# Sheet1.net
KiCad netlist of a schematic drawn in Altium Designer
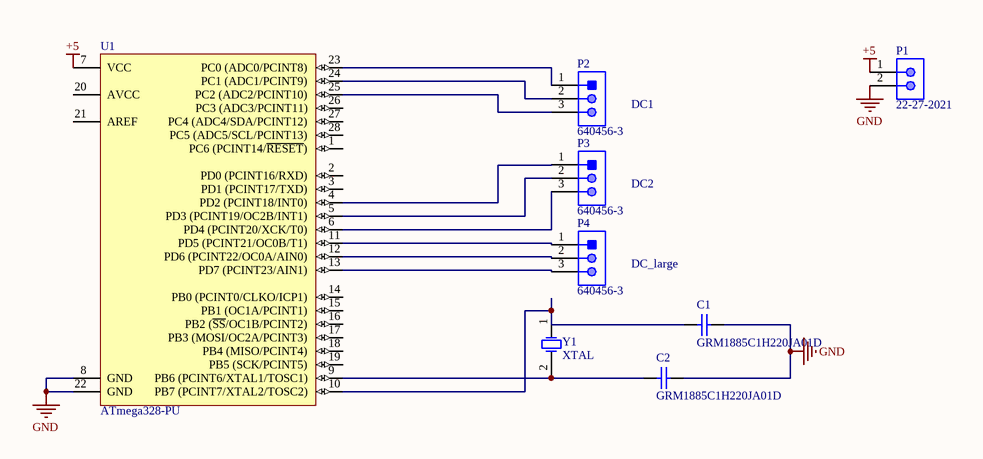
[diagram p0: Sheet1.SchDoc]

(export (version "E")
  (design (tool "Eeschema 10.0.6"))
  (components
    (comp (ref "C1")
      (value "GRM1885C1H220JA01D")
      (footprint "CAPC1608X90X35ML10T15")
      (description "Chip Capacitor, 22 pF, +/- 5%, 50 V, -55 to 125 degC, 0603 (1608 Metric), RoHS, Tape and Reel")
      (fields (field (name "MANUFACTURER") "Murata"))
      (libsource (lib "Altium Content Vault") (part "CAP-NP-2"))
    )
    (comp (ref "C2")
      (value "GRM1885C1H220JA01D")
      (footprint "CAPC1608X90X35ML10T15")
      (description "Chip Capacitor, 22 pF, +/- 5%, 50 V, -55 to 125 degC, 0603 (1608 Metric), RoHS, Tape and Reel")
      (fields (field (name "MANUFACTURER") "Murata"))
      (libsource (lib "Altium Content Vault") (part "CAP-NP-2"))
    )
    (comp (ref "P1")
      (value "22-27-2021")
      (footprint "MOLX-22-27-2021_V")
      (fields (field (name "MANUFACTURER") "Molex") (field (name "PARTNUMBER") "0022272021"))
      (libsource (lib "Altium Content Vault") (part "CN-1P-M-R2"))
    )
    (comp (ref "P2")
      (value "640456-3")
      (footprint "TECO-640456-3")
      (description "Male Header, Pitch 2.54 mm, 1 x 3 Position, Height 10.03 mm, Tail Length 3.56 mm, -55 to 105 degC")
      (fields (field (name "MANUFACTURER") "TE Connectivity"))
      (libsource (lib "Altium Content Vault") (part "CN-1P-M-R3"))
    )
    (comp (ref "P3")
      (value "640456-3")
      (footprint "TECO-640456-3")
      (description "Male Header, Pitch 2.54 mm, 1 x 3 Position, Height 10.03 mm, Tail Length 3.56 mm, -55 to 105 degC")
      (fields (field (name "MANUFACTURER") "TE Connectivity"))
      (libsource (lib "Altium Content Vault") (part "CN-1P-M-R3"))
    )
    (comp (ref "P4")
      (value "640456-3")
      (footprint "TECO-640456-3")
      (description "Male Header, Pitch 2.54 mm, 1 x 3 Position, Height 10.03 mm, Tail Length 3.56 mm, -55 to 105 degC")
      (fields (field (name "MANUFACTURER") "TE Connectivity"))
      (libsource (lib "Altium Content Vault") (part "CN-1P-M-R3"))
    )
    (comp (ref "U1")
      (value "ATmega328-PU")
      (footprint "28P3")
      (libsource (lib "Altium Content Vault") (part "MC-8B-ATM48-IL28"))
    )
    (comp (ref "Y1")
      (value "XTAL")
      (footprint "R38")
      (description "Crystal Oscillator")
      (fields (field (name "PUBLISHER") "Altium Limited"))
      (libsource (lib "Miscellaneous Devices") (part "XTAL"))
    )
  )
  (nets
    (net (code "1") (name "+5") (class "Default")
      (node (ref "P1") (pin "1") (pinfunction "1_1") (pintype "passive"))
      (node (ref "U1") (pin "7") (pinfunction "VCC_7") (pintype "power_in"))
    )
    (net (code "2") (name "GND") (class "Default")
      (node (ref "C1") (pin "2") (pinfunction "2_2") (pintype "passive"))
      (node (ref "C2") (pin "2") (pinfunction "2_2") (pintype "passive"))
      (node (ref "P1") (pin "2") (pinfunction "2_2") (pintype "passive"))
      (node (ref "U1") (pin "22") (pinfunction "GND_22") (pintype "power_in"))
      (node (ref "U1") (pin "8") (pinfunction "GND_8") (pintype "power_in"))
    )
    (net (code "3") (name "Net-(U1-PB6_(PCINT6{slash}XTAL1{slash}TOSC1))") (class "Default")
      (node (ref "C2") (pin "1") (pinfunction "1_1") (pintype "passive"))
      (node (ref "U1") (pin "9") (pinfunction "PB6_(PCINT6/XTAL1/TOSC1)_9") (pintype "bidirectional"))
      (node (ref "Y1") (pin "2") (pinfunction "OSC2_2") (pintype "passive"))
    )
    (net (code "4") (name "Net-(U1-PB7_(PCINT7{slash}XTAL2{slash}TOSC2))") (class "Default")
      (node (ref "C1") (pin "1") (pinfunction "1_1") (pintype "passive"))
      (node (ref "U1") (pin "10") (pinfunction "PB7_(PCINT7/XTAL2/TOSC2)_10") (pintype "bidirectional"))
      (node (ref "Y1") (pin "1") (pinfunction "OSC1_1") (pintype "passive"))
    )
    (net (code "5") (name "Net-(U1-PC0_(ADC0{slash}PCINT8))") (class "Default")
      (node (ref "P2") (pin "1") (pinfunction "1_1") (pintype "passive"))
      (node (ref "U1") (pin "23") (pinfunction "PC0_(ADC0/PCINT8)_23") (pintype "bidirectional"))
    )
    (net (code "6") (name "Net-(U1-PC1_(ADC1{slash}PCINT9))") (class "Default")
      (node (ref "P2") (pin "2") (pinfunction "2_2") (pintype "passive"))
      (node (ref "U1") (pin "24") (pinfunction "PC1_(ADC1/PCINT9)_24") (pintype "bidirectional"))
    )
    (net (code "7") (name "Net-(U1-PC2_(ADC2{slash}PCINT10))") (class "Default")
      (node (ref "P2") (pin "3") (pinfunction "3_3") (pintype "passive"))
      (node (ref "U1") (pin "25") (pinfunction "PC2_(ADC2/PCINT10)_25") (pintype "bidirectional"))
    )
    (net (code "8") (name "Net-(U1-PD2_(PCINT18{slash}INT0))") (class "Default")
      (node (ref "P3") (pin "1") (pinfunction "1_1") (pintype "passive"))
      (node (ref "U1") (pin "4") (pinfunction "PD2_(PCINT18/INT0)_4") (pintype "bidirectional"))
    )
    (net (code "9") (name "Net-(U1-PD3_(PCINT19{slash}OC2B{slash}INT1))") (class "Default")
      (node (ref "P3") (pin "2") (pinfunction "2_2") (pintype "passive"))
      (node (ref "U1") (pin "5") (pinfunction "PD3_(PCINT19/OC2B/INT1)_5") (pintype "bidirectional"))
    )
    (net (code "10") (name "Net-(U1-PD4_(PCINT20{slash}XCK{slash}T0))") (class "Default")
      (node (ref "P3") (pin "3") (pinfunction "3_3") (pintype "passive"))
      (node (ref "U1") (pin "6") (pinfunction "PD4_(PCINT20/XCK/T0)_6") (pintype "bidirectional"))
    )
    (net (code "11") (name "Net-(U1-PD5_(PCINT21{slash}OC0B{slash}T1))") (class "Default")
      (node (ref "P4") (pin "1") (pinfunction "1_1") (pintype "passive"))
      (node (ref "U1") (pin "11") (pinfunction "PD5_(PCINT21/OC0B/T1)_11") (pintype "bidirectional"))
    )
    (net (code "12") (name "Net-(U1-PD6_(PCINT22{slash}OC0A{slash}AIN0))") (class "Default")
      (node (ref "P4") (pin "2") (pinfunction "2_2") (pintype "passive"))
      (node (ref "U1") (pin "12") (pinfunction "PD6_(PCINT22/OC0A/AIN0)_12") (pintype "bidirectional"))
    )
    (net (code "13") (name "Net-(U1-PD7_(PCINT23{slash}AIN1))") (class "Default")
      (node (ref "P4") (pin "3") (pinfunction "3_3") (pintype "passive"))
      (node (ref "U1") (pin "13") (pinfunction "PD7_(PCINT23/AIN1)_13") (pintype "bidirectional"))
    )
    (net (code "14") (name "unconnected-(U1-AREF-Pad21)") (class "Default")
      (node (ref "U1") (pin "21") (pinfunction "AREF_21") (pintype "power_in"))
    )
    (net (code "15") (name "unconnected-(U1-AVCC-Pad20)") (class "Default")
      (node (ref "U1") (pin "20") (pinfunction "AVCC_20") (pintype "power_in"))
    )
    (net (code "16") (name "unconnected-(U1-PB0_(PCINT0{slash}CLKO{slash}ICP1)-Pad14)") (class "Default")
      (node (ref "U1") (pin "14") (pinfunction "PB0_(PCINT0/CLKO/ICP1)_14") (pintype "bidirectional"))
    )
    (net (code "17") (name "unconnected-(U1-PB1_(OC1A{slash}PCINT1)-Pad15)") (class "Default")
      (node (ref "U1") (pin "15") (pinfunction "PB1_(OC1A/PCINT1)_15") (pintype "bidirectional"))
    )
    (net (code "18") (name "unconnected-(U1-PB2_(~{SS}{slash}OC1B{slash}PCINT2)-Pad16)") (class "Default")
      (node (ref "U1") (pin "16") (pinfunction "PB2_(~{SS}/OC1B/PCINT2)_16") (pintype "bidirectional"))
    )
    (net (code "19") (name "unconnected-(U1-PB3_(MOSI{slash}OC2A{slash}PCINT3)-Pad17)") (class "Default")
      (node (ref "U1") (pin "17") (pinfunction "PB3_(MOSI/OC2A/PCINT3)_17") (pintype "bidirectional"))
    )
    (net (code "20") (name "unconnected-(U1-PB4_(MISO{slash}PCINT4)-Pad18)") (class "Default")
      (node (ref "U1") (pin "18") (pinfunction "PB4_(MISO/PCINT4)_18") (pintype "bidirectional"))
    )
    (net (code "21") (name "unconnected-(U1-PB5_(SCK{slash}PCINT5)-Pad19)") (class "Default")
      (node (ref "U1") (pin "19") (pinfunction "PB5_(SCK/PCINT5)_19") (pintype "bidirectional"))
    )
    (net (code "22") (name "unconnected-(U1-PC3_(ADC3{slash}PCINT11)-Pad26)") (class "Default")
      (node (ref "U1") (pin "26") (pinfunction "PC3_(ADC3/PCINT11)_26") (pintype "bidirectional"))
    )
    (net (code "23") (name "unconnected-(U1-PC4_(ADC4{slash}SDA{slash}PCINT12)-Pad27)") (class "Default")
      (node (ref "U1") (pin "27") (pinfunction "PC4_(ADC4/SDA/PCINT12)_27") (pintype "bidirectional"))
    )
    (net (code "24") (name "unconnected-(U1-PC5_(ADC5{slash}SCL{slash}PCINT13)-Pad28)") (class "Default")
      (node (ref "U1") (pin "28") (pinfunction "PC5_(ADC5/SCL/PCINT13)_28") (pintype "bidirectional"))
    )
    (net (code "25") (name "unconnected-(U1-PC6_(PCINT14{slash}~{RESET})-Pad1)") (class "Default")
      (node (ref "U1") (pin "1") (pinfunction "PC6_(PCINT14/~{RESET})_1") (pintype "bidirectional"))
    )
    (net (code "26") (name "unconnected-(U1-PD0_(PCINT16{slash}RXD)-Pad2)") (class "Default")
      (node (ref "U1") (pin "2") (pinfunction "PD0_(PCINT16/RXD)_2") (pintype "bidirectional"))
    )
    (net (code "27") (name "unconnected-(U1-PD1_(PCINT17{slash}TXD)-Pad3)") (class "Default")
      (node (ref "U1") (pin "3") (pinfunction "PD1_(PCINT17/TXD)_3") (pintype "bidirectional"))
    )
  )
)
